# Multi_PWS_V1p0.net
KiCad netlist of a schematic drawn in EAGLE
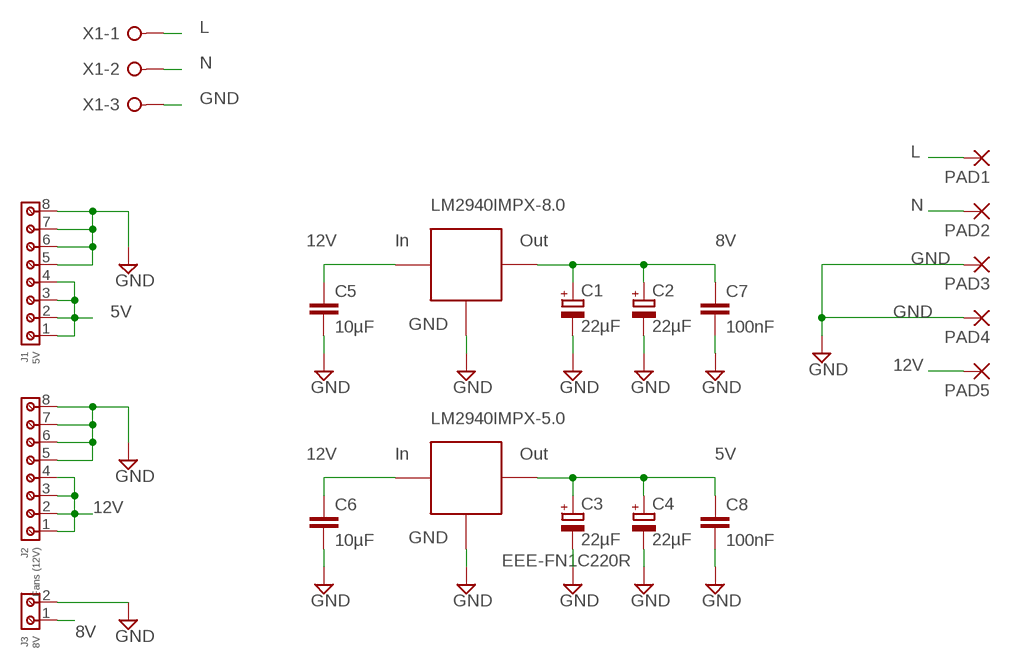
[diagram p0: schematic, sheet 1]

(export (version "E")
  (design (tool "Eeschema 10.0.6"))
  (components
    (comp (ref "C1")
      (value "22µF")
      (footprint "eagle-import:PANASONIC_B")
      (libsource (lib "eagle-import") (part "CPOL-EUB"))
    )
    (comp (ref "C2")
      (value "22µF")
      (footprint "eagle-import:PANASONIC_B")
      (libsource (lib "eagle-import") (part "CPOL-EUB"))
    )
    (comp (ref "C3")
      (value "22µF")
      (footprint "eagle-import:PANASONIC_B")
      (libsource (lib "eagle-import") (part "CPOL-EUB"))
    )
    (comp (ref "C4")
      (value "22µF")
      (footprint "eagle-import:PANASONIC_B")
      (libsource (lib "eagle-import") (part "CPOL-EUB"))
    )
    (comp (ref "C5")
      (value "10µF")
      (footprint "eagle-import:C1210")
      (libsource (lib "eagle-import") (part "C-EUC1210"))
    )
    (comp (ref "C6")
      (value "10µF")
      (footprint "eagle-import:C1210")
      (libsource (lib "eagle-import") (part "C-EUC1210"))
    )
    (comp (ref "C7")
      (value "100nF")
      (footprint "eagle-import:C1210")
      (libsource (lib "eagle-import") (part "C-EUC1210"))
    )
    (comp (ref "C8")
      (value "100nF")
      (footprint "eagle-import:C1210")
      (libsource (lib "eagle-import") (part "C-EUC1210"))
    )
    (comp (ref "J1")
      (value "5V")
      (footprint "eagle-import:691210910008")
      (libsource (lib "eagle-import") (part "691210910008"))
    )
    (comp (ref "J2")
      (value "Fans (12V)")
      (footprint "eagle-import:691210910008")
      (libsource (lib "eagle-import") (part "691210910008"))
    )
    (comp (ref "J3")
      (value "8V")
      (footprint "eagle-import:691210910002")
      (libsource (lib "eagle-import") (part "691210910002"))
    )
    (comp (ref "PAD1")
      (value "SMD5")
      (footprint "eagle-import:SMD2,54-5,08")
      (libsource (lib "eagle-import") (part "SMD5"))
    )
    (comp (ref "PAD2")
      (value "SMD5")
      (footprint "eagle-import:SMD2,54-5,08")
      (libsource (lib "eagle-import") (part "SMD5"))
    )
    (comp (ref "PAD3")
      (value "SMD5")
      (footprint "eagle-import:SMD2,54-5,08")
      (libsource (lib "eagle-import") (part "SMD5"))
    )
    (comp (ref "PAD4")
      (value "SMD5")
      (footprint "eagle-import:SMD2,54-5,08")
      (libsource (lib "eagle-import") (part "SMD5"))
    )
    (comp (ref "PAD5")
      (value "SMD5")
      (footprint "eagle-import:SMD2,54-5,08")
      (libsource (lib "eagle-import") (part "SMD5"))
    )
    (comp (ref "U$1")
      (value "LM2940IMPX-8.0")
      (footprint "eagle-import:SOT223")
      (libsource (lib "eagle-import") (part "LM2940IMP"))
    )
    (comp (ref "U$2")
      (value "LM2940IMPX-5.0")
      (footprint "eagle-import:SOT223")
      (libsource (lib "eagle-import") (part "LM2940IMP"))
    )
    (comp (ref "X1")
      (value "W237-3E")
      (footprint "eagle-import:W237-3E")
      (libsource (lib "eagle-import") (part "W237-3E"))
    )
  )
  (nets
    (net (code "1") (name "/5V") (class "Default")
      (node (ref "C3") (pin "+") (pinfunction "+_+") (pintype "passive"))
      (node (ref "C4") (pin "+") (pinfunction "+_+") (pintype "passive"))
      (node (ref "C8") (pin "1") (pinfunction "1_1") (pintype "passive"))
      (node (ref "J1") (pin "1") (pinfunction "1_1") (pintype "passive"))
      (node (ref "J1") (pin "2") (pinfunction "2_2") (pintype "passive"))
      (node (ref "J1") (pin "3") (pinfunction "3_3") (pintype "passive"))
      (node (ref "J1") (pin "4") (pinfunction "4_4") (pintype "passive"))
      (node (ref "U$2") (pin "3") (pinfunction "VCC_3") (pintype "power_in"))
    )
    (net (code "2") (name "/8V") (class "Default")
      (node (ref "C1") (pin "+") (pinfunction "+_+") (pintype "passive"))
      (node (ref "C2") (pin "+") (pinfunction "+_+") (pintype "passive"))
      (node (ref "C7") (pin "1") (pinfunction "1_1") (pintype "passive"))
      (node (ref "J3") (pin "1") (pinfunction "1_1") (pintype "passive"))
      (node (ref "U$1") (pin "3") (pinfunction "VCC_3") (pintype "power_in"))
    )
    (net (code "3") (name "/12V") (class "Default")
      (node (ref "C5") (pin "1") (pinfunction "1_1") (pintype "passive"))
      (node (ref "C6") (pin "1") (pinfunction "1_1") (pintype "passive"))
      (node (ref "J2") (pin "1") (pinfunction "1_1") (pintype "passive"))
      (node (ref "J2") (pin "2") (pinfunction "2_2") (pintype "passive"))
      (node (ref "J2") (pin "3") (pinfunction "3_3") (pintype "passive"))
      (node (ref "J2") (pin "4") (pinfunction "4_4") (pintype "passive"))
      (node (ref "PAD5") (pin "1") (pinfunction "P_1") (pintype "passive"))
      (node (ref "U$1") (pin "1") (pinfunction "IN_1") (pintype "bidirectional"))
      (node (ref "U$2") (pin "1") (pinfunction "IN_1") (pintype "bidirectional"))
    )
    (net (code "4") (name "/L") (class "Default")
      (node (ref "PAD1") (pin "1") (pinfunction "P_1") (pintype "passive"))
      (node (ref "X1") (pin "1") (pinfunction "KL_1") (pintype "passive"))
    )
    (net (code "5") (name "/N") (class "Default")
      (node (ref "PAD2") (pin "1") (pinfunction "P_1") (pintype "passive"))
      (node (ref "X1") (pin "2") (pinfunction "KL_2") (pintype "passive"))
    )
    (net (code "6") (name "GND") (class "Default")
      (node (ref "C1") (pin "-") (pinfunction "-_-") (pintype "passive"))
      (node (ref "C2") (pin "-") (pinfunction "-_-") (pintype "passive"))
      (node (ref "C3") (pin "-") (pinfunction "-_-") (pintype "passive"))
      (node (ref "C4") (pin "-") (pinfunction "-_-") (pintype "passive"))
      (node (ref "C5") (pin "2") (pinfunction "2_2") (pintype "passive"))
      (node (ref "C6") (pin "2") (pinfunction "2_2") (pintype "passive"))
      (node (ref "C7") (pin "2") (pinfunction "2_2") (pintype "passive"))
      (node (ref "C8") (pin "2") (pinfunction "2_2") (pintype "passive"))
      (node (ref "J1") (pin "5") (pinfunction "5_5") (pintype "passive"))
      (node (ref "J1") (pin "6") (pinfunction "6_6") (pintype "passive"))
      (node (ref "J1") (pin "7") (pinfunction "7_7") (pintype "passive"))
      (node (ref "J1") (pin "8") (pinfunction "8_8") (pintype "passive"))
      (node (ref "J2") (pin "5") (pinfunction "5_5") (pintype "passive"))
      (node (ref "J2") (pin "6") (pinfunction "6_6") (pintype "passive"))
      (node (ref "J2") (pin "7") (pinfunction "7_7") (pintype "passive"))
      (node (ref "J2") (pin "8") (pinfunction "8_8") (pintype "passive"))
      (node (ref "J3") (pin "2") (pinfunction "2_2") (pintype "passive"))
      (node (ref "PAD3") (pin "1") (pinfunction "P_1") (pintype "passive"))
      (node (ref "PAD4") (pin "1") (pinfunction "P_1") (pintype "passive"))
      (node (ref "U$1") (pin "2") (pinfunction "GND_2") (pintype "bidirectional"))
      (node (ref "U$1") (pin "4") (pinfunction "GND_4") (pintype "bidirectional"))
      (node (ref "U$2") (pin "2") (pinfunction "GND_2") (pintype "bidirectional"))
      (node (ref "U$2") (pin "4") (pinfunction "GND_4") (pintype "bidirectional"))
      (node (ref "X1") (pin "3") (pinfunction "KL_3") (pintype "passive"))
    )
  )
)
